# esp8266breakout.net
KiCad netlist of a schematic drawn in EAGLE
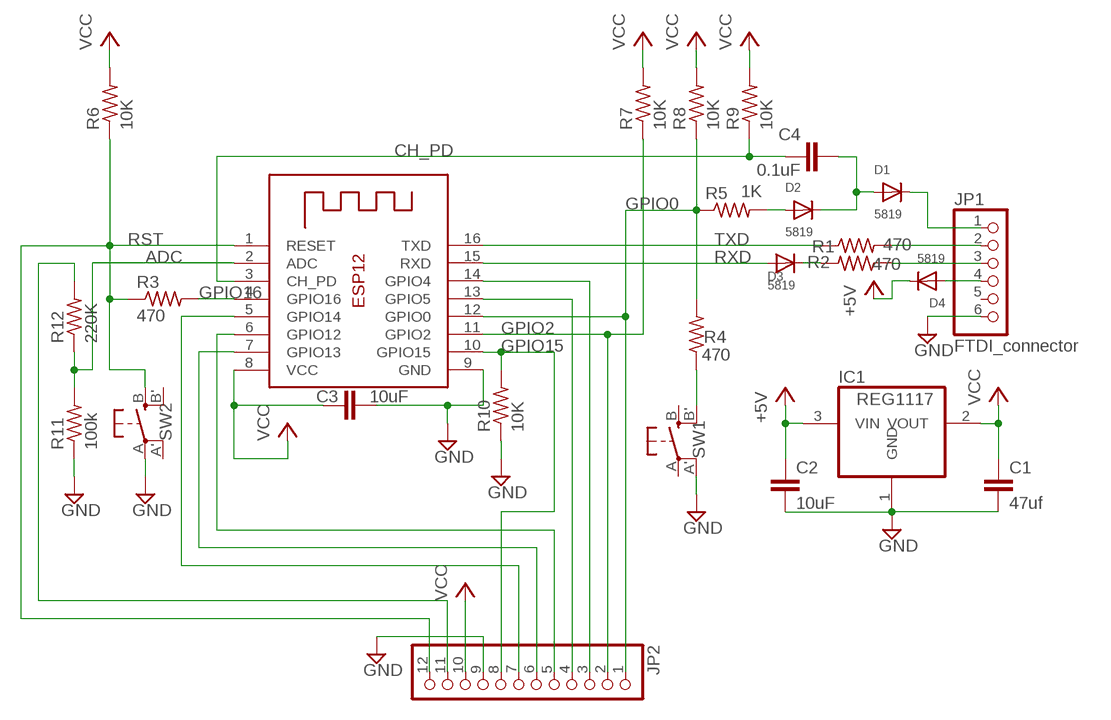
[diagram p0: schematic, sheet 1]

(export (version "E")
  (design (tool "Eeschema 10.0.6"))
  (components
    (comp (ref "C1")
      (value "47uf")
      (footprint "eagle-import:C1206K")
      (libsource (lib "eagle-import") (part "C-EUC1206K"))
    )
    (comp (ref "C2")
      (value "10uF")
      (footprint "eagle-import:C0805K")
      (libsource (lib "eagle-import") (part "C-EUC0805K"))
    )
    (comp (ref "C3")
      (value "10uF")
      (footprint "eagle-import:C0805K")
      (libsource (lib "eagle-import") (part "C-EUC0805K"))
    )
    (comp (ref "C4")
      (value "0.1uF")
      (footprint "eagle-import:C0805K")
      (libsource (lib "eagle-import") (part "C-EUC0805K"))
    )
    (comp (ref "D1")
      (value "5819")
      (footprint "eagle-import:SOD-123")
      (libsource (lib "eagle-import") (part "DIODESOD-123"))
    )
    (comp (ref "D2")
      (value "5819")
      (footprint "eagle-import:SOD-123")
      (libsource (lib "eagle-import") (part "DIODESOD-123"))
    )
    (comp (ref "D3")
      (value "5819")
      (footprint "eagle-import:SOD-123")
      (libsource (lib "eagle-import") (part "DIODESOD-123"))
    )
    (comp (ref "D4")
      (value "5819")
      (footprint "eagle-import:SOD-123")
      (libsource (lib "eagle-import") (part "DIODESOD-123"))
    )
    (comp (ref "IC1")
      (value "REG1117")
      (footprint "eagle-import:SOT223")
      (libsource (lib "eagle-import") (part "REG1117"))
    )
    (comp (ref "JP1")
      (value "FTDI_connector")
      (footprint "eagle-import:1X06-BIGLOCK")
      (libsource (lib "eagle-import") (part "PINHD-1X6LOCK"))
    )
    (comp (ref "JP2")
      (value "PINHD-1X12/90")
      (footprint "eagle-import:1X12_90")
      (libsource (lib "eagle-import") (part "PINHD-1X12/90"))
    )
    (comp (ref "R1")
      (value "470")
      (footprint "eagle-import:R0805")
      (libsource (lib "eagle-import") (part "R-US_R0805"))
    )
    (comp (ref "R2")
      (value "470")
      (footprint "eagle-import:R0805")
      (libsource (lib "eagle-import") (part "R-US_R0805"))
    )
    (comp (ref "R3")
      (value "470")
      (footprint "eagle-import:R0805")
      (libsource (lib "eagle-import") (part "R-US_R0805"))
    )
    (comp (ref "R4")
      (value "470")
      (footprint "eagle-import:R0805")
      (libsource (lib "eagle-import") (part "R-US_R0805"))
    )
    (comp (ref "R5")
      (value "1K")
      (footprint "eagle-import:R0805")
      (libsource (lib "eagle-import") (part "R-US_R0805"))
    )
    (comp (ref "R6")
      (value "10K")
      (footprint "eagle-import:R0805")
      (libsource (lib "eagle-import") (part "R-US_R0805"))
    )
    (comp (ref "R7")
      (value "10K")
      (footprint "eagle-import:R0805")
      (libsource (lib "eagle-import") (part "R-US_R0805"))
    )
    (comp (ref "R8")
      (value "10K")
      (footprint "eagle-import:R0805")
      (libsource (lib "eagle-import") (part "R-US_R0805"))
    )
    (comp (ref "R9")
      (value "10K")
      (footprint "eagle-import:R0805")
      (libsource (lib "eagle-import") (part "R-US_R0805"))
    )
    (comp (ref "R10")
      (value "10K")
      (footprint "eagle-import:R0805")
      (libsource (lib "eagle-import") (part "R-US_R0805"))
    )
    (comp (ref "R11")
      (value "100k")
      (footprint "eagle-import:R0805")
      (libsource (lib "eagle-import") (part "R-US_R0805"))
    )
    (comp (ref "R12")
      (value "220K")
      (footprint "eagle-import:R0805")
      (libsource (lib "eagle-import") (part "R-US_R0805"))
    )
    (comp (ref "SW1")
      (value "6*6mm")
      (footprint "eagle-import:EVQ-Q2")
      (libsource (lib "eagle-import") (part "SPST_TACT-EVQQ2"))
    )
    (comp (ref "SW2")
      (value "6*6mm")
      (footprint "eagle-import:EVQ-Q2")
      (libsource (lib "eagle-import") (part "SPST_TACT-EVQQ2"))
    )
    (comp (ref "X1")
      (value "ESP_12S")
      (footprint "eagle-import:ESP-12")
      (libsource (lib "eagle-import") (part "ESP-12"))
    )
  )
  (nets
    (net (code "1") (name "+5V") (class "Default")
      (node (ref "C2") (pin "1") (pinfunction "1_1") (pintype "passive"))
      (node (ref "D4") (pin "C") (pinfunction "C_C") (pintype "passive"))
      (node (ref "IC1") (pin "3") (pinfunction "VIN_3") (pintype "input"))
    )
    (net (code "2") (name "/ADC") (class "Default")
      (node (ref "R11") (pin "2") (pinfunction "2_2") (pintype "passive"))
      (node (ref "R12") (pin "1") (pinfunction "1_1") (pintype "passive"))
      (node (ref "X1") (pin "2") (pinfunction "ADC_2") (pintype "passive"))
    )
    (net (code "3") (name "/CH_PD") (class "Default")
      (node (ref "C4") (pin "1") (pinfunction "1_1") (pintype "passive"))
      (node (ref "R9") (pin "1") (pinfunction "1_1") (pintype "passive"))
      (node (ref "X1") (pin "3") (pinfunction "CH_PD_3") (pintype "input"))
    )
    (net (code "4") (name "/GPIO0") (class "Default")
      (node (ref "JP2") (pin "1") (pinfunction "1_1") (pintype "passive"))
      (node (ref "R4") (pin "2") (pinfunction "2_2") (pintype "passive"))
      (node (ref "R5") (pin "1") (pinfunction "1_1") (pintype "passive"))
      (node (ref "R8") (pin "1") (pinfunction "1_1") (pintype "passive"))
      (node (ref "X1") (pin "12") (pinfunction "GPIO0_12") (pintype "bidirectional"))
    )
    (net (code "5") (name "/GPIO2") (class "Default")
      (node (ref "JP2") (pin "2") (pinfunction "2_2") (pintype "passive"))
      (node (ref "R7") (pin "1") (pinfunction "1_1") (pintype "passive"))
      (node (ref "X1") (pin "11") (pinfunction "GPIO2_11") (pintype "bidirectional"))
    )
    (net (code "6") (name "/GPIO15") (class "Default")
      (node (ref "JP2") (pin "8") (pinfunction "8_8") (pintype "passive"))
      (node (ref "R10") (pin "2") (pinfunction "2_2") (pintype "passive"))
      (node (ref "X1") (pin "10") (pinfunction "GPIO15_10") (pintype "bidirectional"))
    )
    (net (code "7") (name "/GPIO16") (class "Default")
      (node (ref "R3") (pin "2") (pinfunction "2_2") (pintype "passive"))
      (node (ref "X1") (pin "4") (pinfunction "GPIO16_4") (pintype "bidirectional"))
    )
    (net (code "8") (name "/RST") (class "Default")
      (node (ref "JP2") (pin "12") (pinfunction "12_12") (pintype "passive"))
      (node (ref "R3") (pin "1") (pinfunction "1_1") (pintype "passive"))
      (node (ref "R6") (pin "1") (pinfunction "1_1") (pintype "passive"))
      (node (ref "SW2") (pin "B") (pinfunction "S_B") (pintype "passive"))
      (node (ref "X1") (pin "1") (pinfunction "RESET_1") (pintype "input"))
    )
    (net (code "9") (name "/RXD") (class "Default")
      (node (ref "D3") (pin "A") (pinfunction "A_A") (pintype "passive"))
      (node (ref "X1") (pin "15") (pinfunction "RXD_15") (pintype "input"))
    )
    (net (code "10") (name "/TXD") (class "Default")
      (node (ref "R1") (pin "1") (pinfunction "1_1") (pintype "passive"))
      (node (ref "X1") (pin "16") (pinfunction "TXD_16") (pintype "output"))
    )
    (net (code "11") (name "GND") (class "Default")
      (node (ref "C1") (pin "2") (pinfunction "2_2") (pintype "passive"))
      (node (ref "C2") (pin "2") (pinfunction "2_2") (pintype "passive"))
      (node (ref "C3") (pin "2") (pinfunction "2_2") (pintype "passive"))
      (node (ref "IC1") (pin "1") (pinfunction "GND_1") (pintype "power_in"))
      (node (ref "JP1") (pin "6") (pinfunction "6_6") (pintype "passive"))
      (node (ref "JP2") (pin "9") (pinfunction "9_9") (pintype "passive"))
      (node (ref "R10") (pin "1") (pinfunction "1_1") (pintype "passive"))
      (node (ref "R11") (pin "1") (pinfunction "1_1") (pintype "passive"))
      (node (ref "SW1") (pin "A'") (pinfunction "P1_A'") (pintype "passive"))
      (node (ref "SW2") (pin "A") (pinfunction "P_A") (pintype "passive"))
      (node (ref "X1") (pin "9") (pinfunction "GND_9") (pintype "power_in"))
    )
    (net (code "12") (name "Net-(C4-Pad2)") (class "Default")
      (node (ref "C4") (pin "2") (pinfunction "2_2") (pintype "passive"))
      (node (ref "D1") (pin "A") (pinfunction "A_A") (pintype "passive"))
      (node (ref "D2") (pin "C") (pinfunction "C_C") (pintype "passive"))
    )
    (net (code "13") (name "Net-(D1-PadC)") (class "Default")
      (node (ref "D1") (pin "C") (pinfunction "C_C") (pintype "passive"))
      (node (ref "JP1") (pin "1") (pinfunction "1_1") (pintype "passive"))
    )
    (net (code "14") (name "Net-(D2-PadA)") (class "Default")
      (node (ref "D2") (pin "A") (pinfunction "A_A") (pintype "passive"))
      (node (ref "R5") (pin "2") (pinfunction "2_2") (pintype "passive"))
    )
    (net (code "15") (name "Net-(D3-PadC)") (class "Default")
      (node (ref "D3") (pin "C") (pinfunction "C_C") (pintype "passive"))
      (node (ref "R2") (pin "2") (pinfunction "2_2") (pintype "passive"))
    )
    (net (code "16") (name "Net-(D4-PadA)") (class "Default")
      (node (ref "D4") (pin "A") (pinfunction "A_A") (pintype "passive"))
      (node (ref "JP1") (pin "4") (pinfunction "4_4") (pintype "passive"))
    )
    (net (code "17") (name "Net-(JP1-Pad2)") (class "Default")
      (node (ref "JP1") (pin "2") (pinfunction "2_2") (pintype "passive"))
      (node (ref "R1") (pin "2") (pinfunction "2_2") (pintype "passive"))
    )
    (net (code "18") (name "Net-(JP1-Pad3)") (class "Default")
      (node (ref "JP1") (pin "3") (pinfunction "3_3") (pintype "passive"))
      (node (ref "R2") (pin "1") (pinfunction "1_1") (pintype "passive"))
    )
    (net (code "19") (name "Net-(JP2-Pad11)") (class "Default")
      (node (ref "JP2") (pin "11") (pinfunction "11_11") (pintype "passive"))
      (node (ref "R12") (pin "2") (pinfunction "2_2") (pintype "passive"))
    )
    (net (code "20") (name "Net-(SW1-S1)") (class "Default")
      (node (ref "R4") (pin "1") (pinfunction "1_1") (pintype "passive"))
      (node (ref "SW1") (pin "B'") (pinfunction "S1_B'") (pintype "passive"))
    )
    (net (code "21") (name "Net-(X1-GPIO4)") (class "Default")
      (node (ref "JP2") (pin "3") (pinfunction "3_3") (pintype "passive"))
      (node (ref "X1") (pin "14") (pinfunction "GPIO4_14") (pintype "bidirectional"))
    )
    (net (code "22") (name "Net-(X1-GPIO5)") (class "Default")
      (node (ref "JP2") (pin "4") (pinfunction "4_4") (pintype "passive"))
      (node (ref "X1") (pin "13") (pinfunction "GPIO5_13") (pintype "bidirectional"))
    )
    (net (code "23") (name "Net-(X1-GPIO12)") (class "Default")
      (node (ref "JP2") (pin "5") (pinfunction "5_5") (pintype "passive"))
      (node (ref "X1") (pin "6") (pinfunction "GPIO12_6") (pintype "bidirectional"))
    )
    (net (code "24") (name "Net-(X1-GPIO13)") (class "Default")
      (node (ref "JP2") (pin "6") (pinfunction "6_6") (pintype "passive"))
      (node (ref "X1") (pin "7") (pinfunction "GPIO13_7") (pintype "bidirectional"))
    )
    (net (code "25") (name "Net-(X1-GPIO14)") (class "Default")
      (node (ref "JP2") (pin "7") (pinfunction "7_7") (pintype "passive"))
      (node (ref "X1") (pin "5") (pinfunction "GPIO14_5") (pintype "bidirectional"))
    )
    (net (code "26") (name "VCC") (class "Default")
      (node (ref "C1") (pin "1") (pinfunction "1_1") (pintype "passive"))
      (node (ref "C3") (pin "1") (pinfunction "1_1") (pintype "passive"))
      (node (ref "IC1") (pin "2") (pinfunction "VOUT_2") (pintype "output"))
      (node (ref "JP2") (pin "10") (pinfunction "10_10") (pintype "passive"))
      (node (ref "R6") (pin "2") (pinfunction "2_2") (pintype "passive"))
      (node (ref "R7") (pin "2") (pinfunction "2_2") (pintype "passive"))
      (node (ref "R8") (pin "2") (pinfunction "2_2") (pintype "passive"))
      (node (ref "R9") (pin "2") (pinfunction "2_2") (pintype "passive"))
      (node (ref "X1") (pin "8") (pinfunction "VCC_8") (pintype "power_in"))
    )
    (net (code "27") (name "unconnected-(JP1-Pad5)") (class "Default")
      (node (ref "JP1") (pin "5") (pinfunction "5_5") (pintype "passive"))
    )
    (net (code "28") (name "unconnected-(SW1-P-PadA)") (class "Default")
      (node (ref "SW1") (pin "A") (pinfunction "P_A") (pintype "passive"))
    )
    (net (code "29") (name "unconnected-(SW1-S-PadB)") (class "Default")
      (node (ref "SW1") (pin "B") (pinfunction "S_B") (pintype "passive"))
    )
    (net (code "30") (name "unconnected-(SW2-P1-PadA')") (class "Default")
      (node (ref "SW2") (pin "A'") (pinfunction "P1_A'") (pintype "passive"))
    )
    (net (code "31") (name "unconnected-(SW2-S1-PadB')") (class "Default")
      (node (ref "SW2") (pin "B'") (pinfunction "S1_B'") (pintype "passive"))
    )
  )
)
